# balance.net
KiCad netlist of a schematic drawn in EAGLE
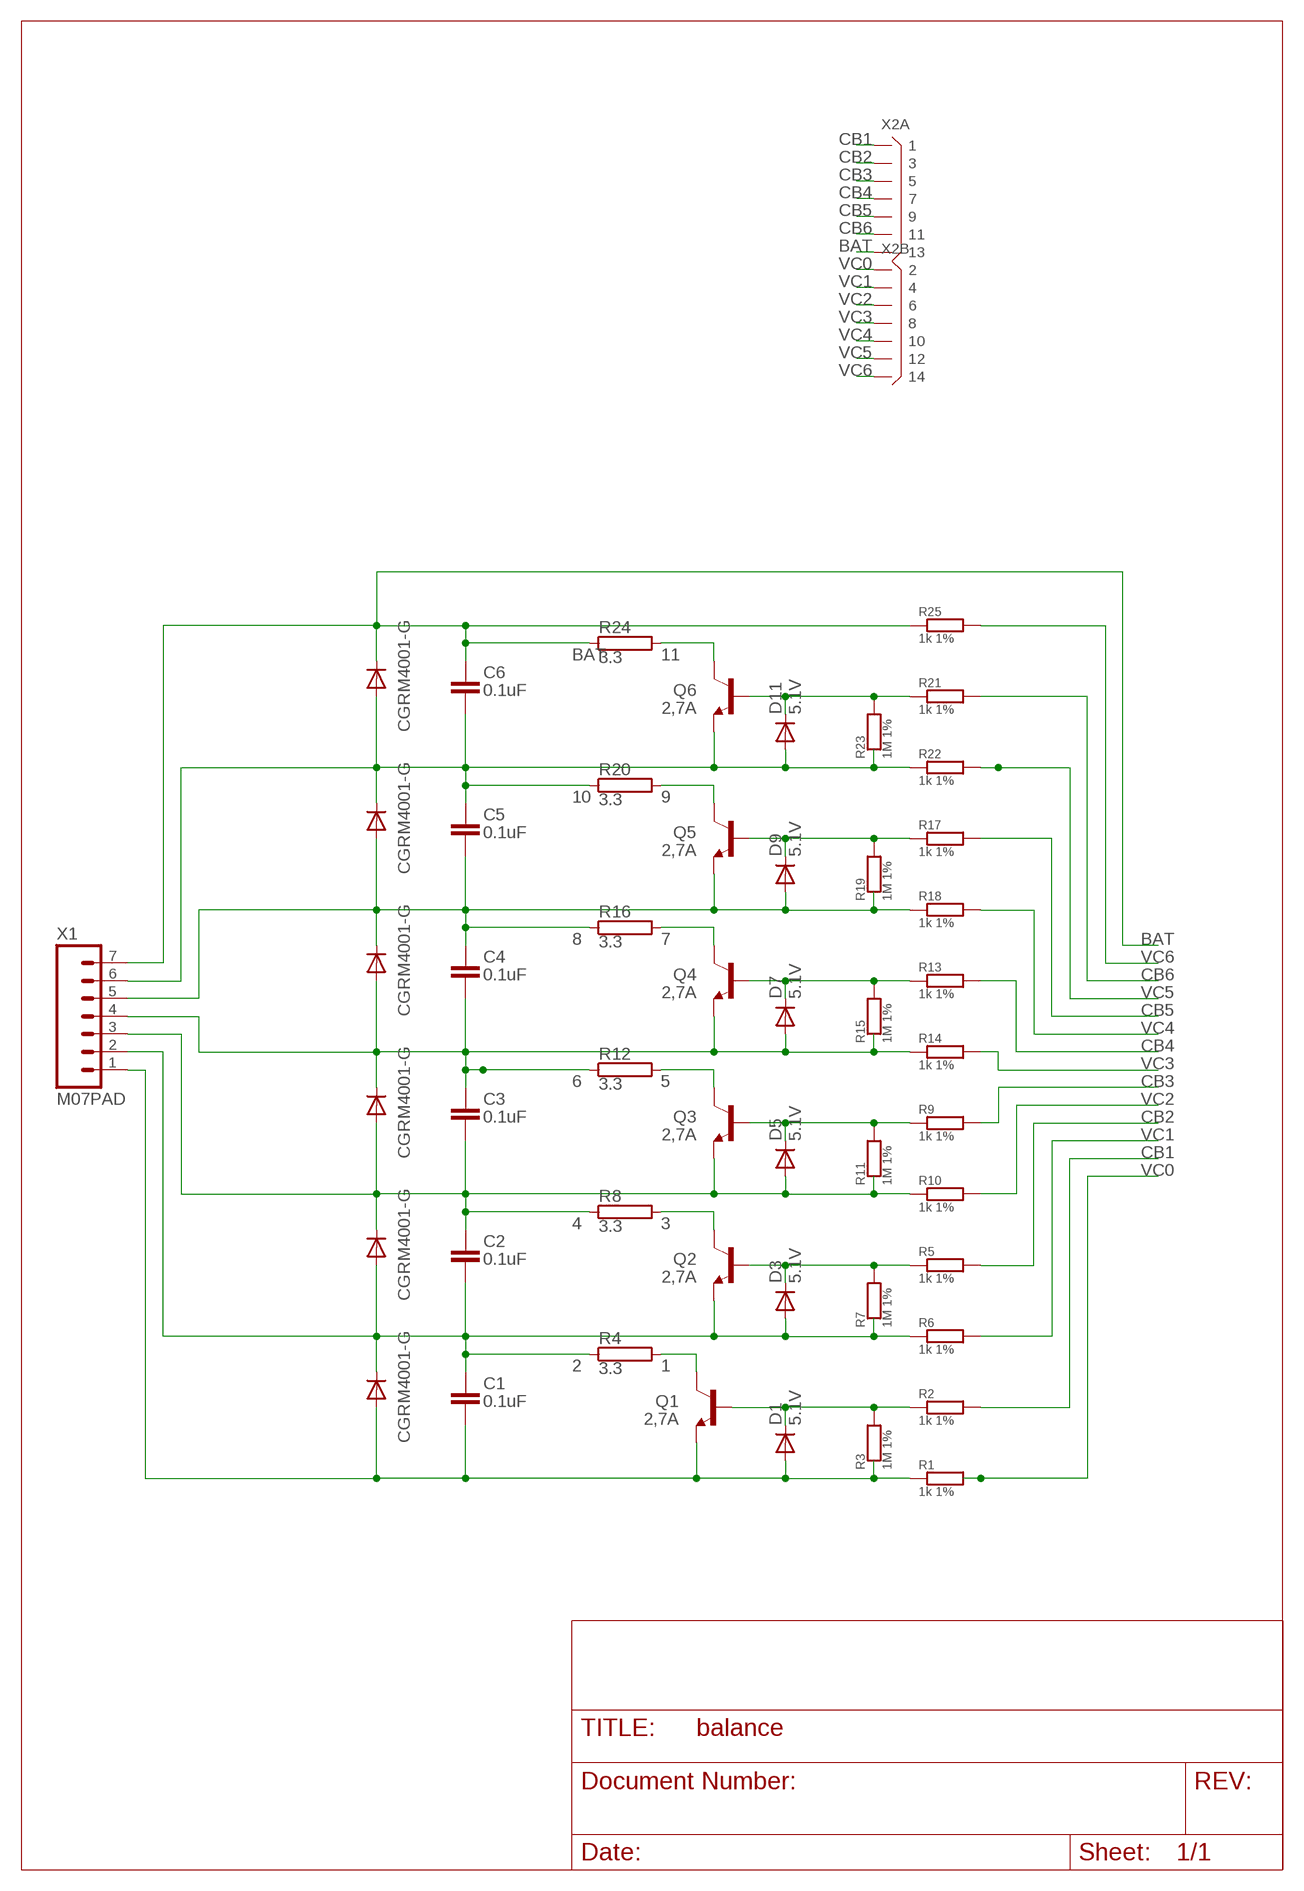
[diagram p0: schematic, sheet 1]

(export (version "E")
  (design (tool "Eeschema 10.0.6"))
  (components
    (comp (ref "C1")
      (value "0.1uF")
      (footprint "eagle-import:C0805")
      (libsource (lib "eagle-import") (part "CSTD"))
    )
    (comp (ref "C2")
      (value "0.1uF")
      (footprint "eagle-import:C0805")
      (libsource (lib "eagle-import") (part "CSTD"))
    )
    (comp (ref "C3")
      (value "0.1uF")
      (footprint "eagle-import:C0805")
      (libsource (lib "eagle-import") (part "CSTD"))
    )
    (comp (ref "C4")
      (value "0.1uF")
      (footprint "eagle-import:C0805")
      (libsource (lib "eagle-import") (part "CSTD"))
    )
    (comp (ref "C5")
      (value "0.1uF")
      (footprint "eagle-import:C0805")
      (libsource (lib "eagle-import") (part "CSTD"))
    )
    (comp (ref "C6")
      (value "0.1uF")
      (footprint "eagle-import:C0805")
      (libsource (lib "eagle-import") (part "CSTD"))
    )
    (comp (ref "D1")
      (value "5.1V")
      (footprint "eagle-import:SOD-323")
      (libsource (lib "eagle-import") (part "DIODESOD"))
    )
    (comp (ref "D2")
      (value "CGRM4001-G")
      (footprint "eagle-import:SOD-123_MINI-SMA")
      (libsource (lib "eagle-import") (part "CGRM400-G1"))
    )
    (comp (ref "D3")
      (value "5.1V")
      (footprint "eagle-import:SOD-323")
      (libsource (lib "eagle-import") (part "DIODESOD"))
    )
    (comp (ref "D4")
      (value "CGRM4001-G")
      (footprint "eagle-import:SOD-123_MINI-SMA")
      (libsource (lib "eagle-import") (part "CGRM400-G1"))
    )
    (comp (ref "D5")
      (value "5.1V")
      (footprint "eagle-import:SOD-323")
      (libsource (lib "eagle-import") (part "DIODESOD"))
    )
    (comp (ref "D6")
      (value "CGRM4001-G")
      (footprint "eagle-import:SOD-123_MINI-SMA")
      (libsource (lib "eagle-import") (part "CGRM400-G1"))
    )
    (comp (ref "D7")
      (value "5.1V")
      (footprint "eagle-import:SOD-323")
      (libsource (lib "eagle-import") (part "DIODESOD"))
    )
    (comp (ref "D8")
      (value "CGRM4001-G")
      (footprint "eagle-import:SOD-123_MINI-SMA")
      (libsource (lib "eagle-import") (part "CGRM400-G1"))
    )
    (comp (ref "D9")
      (value "5.1V")
      (footprint "eagle-import:SOD-323")
      (libsource (lib "eagle-import") (part "DIODESOD"))
    )
    (comp (ref "D10")
      (value "CGRM4001-G")
      (footprint "eagle-import:SOD-123_MINI-SMA")
      (libsource (lib "eagle-import") (part "CGRM400-G1"))
    )
    (comp (ref "D11")
      (value "5.1V")
      (footprint "eagle-import:SOD-323")
      (libsource (lib "eagle-import") (part "DIODESOD"))
    )
    (comp (ref "D12")
      (value "CGRM4001-G")
      (footprint "eagle-import:SOD-123_MINI-SMA")
      (libsource (lib "eagle-import") (part "CGRM400-G1"))
    )
    (comp (ref "Q1")
      (value "2,7A")
      (footprint "eagle-import:SOT23")
      (libsource (lib "eagle-import") (part "TRANSISTOR_NPNSOT23"))
    )
    (comp (ref "Q2")
      (value "2,7A")
      (footprint "eagle-import:SOT23")
      (libsource (lib "eagle-import") (part "TRANSISTOR_NPNSOT23"))
    )
    (comp (ref "Q3")
      (value "2,7A")
      (footprint "eagle-import:SOT23")
      (libsource (lib "eagle-import") (part "TRANSISTOR_NPNSOT23"))
    )
    (comp (ref "Q4")
      (value "2,7A")
      (footprint "eagle-import:SOT23")
      (libsource (lib "eagle-import") (part "TRANSISTOR_NPNSOT23"))
    )
    (comp (ref "Q5")
      (value "2,7A")
      (footprint "eagle-import:SOT23")
      (libsource (lib "eagle-import") (part "TRANSISTOR_NPNSOT23"))
    )
    (comp (ref "Q6")
      (value "2,7A")
      (footprint "eagle-import:SOT23")
      (libsource (lib "eagle-import") (part "TRANSISTOR_NPNSOT23"))
    )
    (comp (ref "R1")
      (value "1k 1%")
      (footprint "eagle-import:R0805")
      (libsource (lib "eagle-import") (part "R"))
    )
    (comp (ref "R2")
      (value "1k 1%")
      (footprint "eagle-import:R0805")
      (libsource (lib "eagle-import") (part "R"))
    )
    (comp (ref "R3")
      (value "1M 1%")
      (footprint "eagle-import:R0805")
      (libsource (lib "eagle-import") (part "R"))
    )
    (comp (ref "R4")
      (value "3.3")
      (footprint "eagle-import:HS15")
      (fields (field (name "MF") "OHMITE") (field (name "MPN") "RHS15KE"))
      (libsource (lib "eagle-import") (part "RHS15"))
    )
    (comp (ref "R5")
      (value "1k 1%")
      (footprint "eagle-import:R0805")
      (libsource (lib "eagle-import") (part "R"))
    )
    (comp (ref "R6")
      (value "1k 1%")
      (footprint "eagle-import:R0805")
      (libsource (lib "eagle-import") (part "R"))
    )
    (comp (ref "R7")
      (value "1M 1%")
      (footprint "eagle-import:R0805")
      (libsource (lib "eagle-import") (part "R"))
    )
    (comp (ref "R8")
      (value "3.3")
      (footprint "eagle-import:HS15")
      (fields (field (name "MF") "OHMITE") (field (name "MPN") "RHS15KE"))
      (libsource (lib "eagle-import") (part "RHS15"))
    )
    (comp (ref "R9")
      (value "1k 1%")
      (footprint "eagle-import:R0805")
      (libsource (lib "eagle-import") (part "R"))
    )
    (comp (ref "R10")
      (value "1k 1%")
      (footprint "eagle-import:R0805")
      (libsource (lib "eagle-import") (part "R"))
    )
    (comp (ref "R11")
      (value "1M 1%")
      (footprint "eagle-import:R0805")
      (libsource (lib "eagle-import") (part "R"))
    )
    (comp (ref "R12")
      (value "3.3")
      (footprint "eagle-import:HS15")
      (fields (field (name "MF") "OHMITE") (field (name "MPN") "RHS15KE"))
      (libsource (lib "eagle-import") (part "RHS15"))
    )
    (comp (ref "R13")
      (value "1k 1%")
      (footprint "eagle-import:R0805")
      (libsource (lib "eagle-import") (part "R"))
    )
    (comp (ref "R14")
      (value "1k 1%")
      (footprint "eagle-import:R0805")
      (libsource (lib "eagle-import") (part "R"))
    )
    (comp (ref "R15")
      (value "1M 1%")
      (footprint "eagle-import:R0805")
      (libsource (lib "eagle-import") (part "R"))
    )
    (comp (ref "R16")
      (value "3.3")
      (footprint "eagle-import:HS15")
      (fields (field (name "MF") "OHMITE") (field (name "MPN") "RHS15KE"))
      (libsource (lib "eagle-import") (part "RHS15"))
    )
    (comp (ref "R17")
      (value "1k 1%")
      (footprint "eagle-import:R0805")
      (libsource (lib "eagle-import") (part "R"))
    )
    (comp (ref "R18")
      (value "1k 1%")
      (footprint "eagle-import:R0805")
      (libsource (lib "eagle-import") (part "R"))
    )
    (comp (ref "R19")
      (value "1M 1%")
      (footprint "eagle-import:R0805")
      (libsource (lib "eagle-import") (part "R"))
    )
    (comp (ref "R20")
      (value "3.3")
      (footprint "eagle-import:HS15")
      (fields (field (name "MF") "OHMITE") (field (name "MPN") "RHS15KE"))
      (libsource (lib "eagle-import") (part "RHS15"))
    )
    (comp (ref "R21")
      (value "1k 1%")
      (footprint "eagle-import:R0805")
      (libsource (lib "eagle-import") (part "R"))
    )
    (comp (ref "R22")
      (value "1k 1%")
      (footprint "eagle-import:R0805")
      (libsource (lib "eagle-import") (part "R"))
    )
    (comp (ref "R23")
      (value "1M 1%")
      (footprint "eagle-import:R0805")
      (libsource (lib "eagle-import") (part "R"))
    )
    (comp (ref "R24")
      (value "3.3")
      (footprint "eagle-import:HS15")
      (fields (field (name "MF") "OHMITE") (field (name "MPN") "RHS15KE"))
      (libsource (lib "eagle-import") (part "RHS15"))
    )
    (comp (ref "R25")
      (value "1k 1%")
      (footprint "eagle-import:R0805")
      (libsource (lib "eagle-import") (part "R"))
    )
    (comp (ref "X1")
      (value "M07PAD")
      (footprint "eagle-import:1X07")
      (libsource (lib "eagle-import") (part "M07PAD"))
    )
    (comp (ref "X2")
      (value "X07X2IR")
      (footprint "eagle-import:X14R-IDC")
      (libsource (lib "eagle-import") (part "X07X2IR"))
    )
  )
  (nets
    (net (code "1") (name "/1") (class "Default")
      (node (ref "Q1") (pin "3") (pinfunction "C_3") (pintype "passive"))
      (node (ref "R4") (pin "2") (pinfunction "2_2") (pintype "passive"))
    )
    (net (code "2") (name "/2") (class "Default")
      (node (ref "C1") (pin "2") (pinfunction "2_2") (pintype "passive"))
      (node (ref "C2") (pin "1") (pinfunction "1_1") (pintype "passive"))
      (node (ref "D2") (pin "C") (pinfunction "C_C") (pintype "passive"))
      (node (ref "D3") (pin "2") (pinfunction "A_2") (pintype "passive"))
      (node (ref "D4") (pin "A") (pinfunction "A_A") (pintype "passive"))
      (node (ref "Q2") (pin "2") (pinfunction "E_2") (pintype "passive"))
      (node (ref "R4") (pin "1") (pinfunction "1_1") (pintype "passive"))
      (node (ref "R6") (pin "1") (pinfunction "1_1") (pintype "passive"))
      (node (ref "R7") (pin "1") (pinfunction "1_1") (pintype "passive"))
      (node (ref "X1") (pin "2") (pinfunction "2_2") (pintype "passive"))
    )
    (net (code "3") (name "/3") (class "Default")
      (node (ref "Q2") (pin "3") (pinfunction "C_3") (pintype "passive"))
      (node (ref "R8") (pin "2") (pinfunction "2_2") (pintype "passive"))
    )
    (net (code "4") (name "/4") (class "Default")
      (node (ref "C2") (pin "2") (pinfunction "2_2") (pintype "passive"))
      (node (ref "C3") (pin "1") (pinfunction "1_1") (pintype "passive"))
      (node (ref "D4") (pin "C") (pinfunction "C_C") (pintype "passive"))
      (node (ref "D5") (pin "2") (pinfunction "A_2") (pintype "passive"))
      (node (ref "D6") (pin "A") (pinfunction "A_A") (pintype "passive"))
      (node (ref "Q3") (pin "2") (pinfunction "E_2") (pintype "passive"))
      (node (ref "R10") (pin "1") (pinfunction "1_1") (pintype "passive"))
      (node (ref "R11") (pin "1") (pinfunction "1_1") (pintype "passive"))
      (node (ref "R8") (pin "1") (pinfunction "1_1") (pintype "passive"))
      (node (ref "X1") (pin "3") (pinfunction "3_3") (pintype "passive"))
    )
    (net (code "5") (name "/5") (class "Default")
      (node (ref "Q3") (pin "3") (pinfunction "C_3") (pintype "passive"))
      (node (ref "R12") (pin "2") (pinfunction "2_2") (pintype "passive"))
    )
    (net (code "6") (name "/6") (class "Default")
      (node (ref "C3") (pin "2") (pinfunction "2_2") (pintype "passive"))
      (node (ref "C4") (pin "1") (pinfunction "1_1") (pintype "passive"))
      (node (ref "D6") (pin "C") (pinfunction "C_C") (pintype "passive"))
      (node (ref "D7") (pin "2") (pinfunction "A_2") (pintype "passive"))
      (node (ref "D8") (pin "A") (pinfunction "A_A") (pintype "passive"))
      (node (ref "Q4") (pin "2") (pinfunction "E_2") (pintype "passive"))
      (node (ref "R12") (pin "1") (pinfunction "1_1") (pintype "passive"))
      (node (ref "R14") (pin "1") (pinfunction "1_1") (pintype "passive"))
      (node (ref "R15") (pin "1") (pinfunction "1_1") (pintype "passive"))
      (node (ref "X1") (pin "4") (pinfunction "4_4") (pintype "passive"))
    )
    (net (code "7") (name "/7") (class "Default")
      (node (ref "Q4") (pin "3") (pinfunction "C_3") (pintype "passive"))
      (node (ref "R16") (pin "2") (pinfunction "2_2") (pintype "passive"))
    )
    (net (code "8") (name "/8") (class "Default")
      (node (ref "C4") (pin "2") (pinfunction "2_2") (pintype "passive"))
      (node (ref "C5") (pin "1") (pinfunction "1_1") (pintype "passive"))
      (node (ref "D10") (pin "A") (pinfunction "A_A") (pintype "passive"))
      (node (ref "D8") (pin "C") (pinfunction "C_C") (pintype "passive"))
      (node (ref "D9") (pin "2") (pinfunction "A_2") (pintype "passive"))
      (node (ref "Q5") (pin "2") (pinfunction "E_2") (pintype "passive"))
      (node (ref "R16") (pin "1") (pinfunction "1_1") (pintype "passive"))
      (node (ref "R18") (pin "1") (pinfunction "1_1") (pintype "passive"))
      (node (ref "R19") (pin "1") (pinfunction "1_1") (pintype "passive"))
      (node (ref "X1") (pin "5") (pinfunction "5_5") (pintype "passive"))
    )
    (net (code "9") (name "/9") (class "Default")
      (node (ref "Q5") (pin "3") (pinfunction "C_3") (pintype "passive"))
      (node (ref "R20") (pin "2") (pinfunction "2_2") (pintype "passive"))
    )
    (net (code "10") (name "/10") (class "Default")
      (node (ref "C5") (pin "2") (pinfunction "2_2") (pintype "passive"))
      (node (ref "C6") (pin "1") (pinfunction "1_1") (pintype "passive"))
      (node (ref "D10") (pin "C") (pinfunction "C_C") (pintype "passive"))
      (node (ref "D11") (pin "2") (pinfunction "A_2") (pintype "passive"))
      (node (ref "D12") (pin "A") (pinfunction "A_A") (pintype "passive"))
      (node (ref "Q6") (pin "2") (pinfunction "E_2") (pintype "passive"))
      (node (ref "R20") (pin "1") (pinfunction "1_1") (pintype "passive"))
      (node (ref "R22") (pin "1") (pinfunction "1_1") (pintype "passive"))
      (node (ref "R23") (pin "1") (pinfunction "1_1") (pintype "passive"))
      (node (ref "X1") (pin "6") (pinfunction "6_6") (pintype "passive"))
    )
    (net (code "11") (name "/11") (class "Default")
      (node (ref "Q6") (pin "3") (pinfunction "C_3") (pintype "passive"))
      (node (ref "R24") (pin "2") (pinfunction "2_2") (pintype "passive"))
    )
    (net (code "12") (name "/BAT") (class "Default")
      (node (ref "C6") (pin "2") (pinfunction "2_2") (pintype "passive"))
      (node (ref "D12") (pin "C") (pinfunction "C_C") (pintype "passive"))
      (node (ref "R24") (pin "1") (pinfunction "1_1") (pintype "passive"))
      (node (ref "R25") (pin "1") (pinfunction "1_1") (pintype "passive"))
      (node (ref "X1") (pin "7") (pinfunction "7_7") (pintype "passive"))
      (node (ref "X2") (pin "13") (pinfunction "13_13") (pintype "bidirectional"))
    )
    (net (code "13") (name "/CB1") (class "Default")
      (node (ref "R2") (pin "2") (pinfunction "2_2") (pintype "passive"))
      (node (ref "X2") (pin "1") (pinfunction "1_1") (pintype "bidirectional"))
    )
    (net (code "14") (name "/CB2") (class "Default")
      (node (ref "R5") (pin "2") (pinfunction "2_2") (pintype "passive"))
      (node (ref "X2") (pin "3") (pinfunction "3_3") (pintype "bidirectional"))
    )
    (net (code "15") (name "/CB3") (class "Default")
      (node (ref "R9") (pin "2") (pinfunction "2_2") (pintype "passive"))
      (node (ref "X2") (pin "5") (pinfunction "5_5") (pintype "bidirectional"))
    )
    (net (code "16") (name "/CB4") (class "Default")
      (node (ref "R13") (pin "2") (pinfunction "2_2") (pintype "passive"))
      (node (ref "X2") (pin "7") (pinfunction "7_7") (pintype "bidirectional"))
    )
    (net (code "17") (name "/CB5") (class "Default")
      (node (ref "R17") (pin "2") (pinfunction "2_2") (pintype "passive"))
      (node (ref "X2") (pin "9") (pinfunction "9_9") (pintype "bidirectional"))
    )
    (net (code "18") (name "/CB6") (class "Default")
      (node (ref "R21") (pin "2") (pinfunction "2_2") (pintype "passive"))
      (node (ref "X2") (pin "11") (pinfunction "11_11") (pintype "bidirectional"))
    )
    (net (code "19") (name "/VC0") (class "Default")
      (node (ref "R1") (pin "2") (pinfunction "2_2") (pintype "passive"))
      (node (ref "X2") (pin "2") (pinfunction "2_2") (pintype "bidirectional"))
    )
    (net (code "20") (name "/VC1") (class "Default")
      (node (ref "R6") (pin "2") (pinfunction "2_2") (pintype "passive"))
      (node (ref "X2") (pin "4") (pinfunction "4_4") (pintype "bidirectional"))
    )
    (net (code "21") (name "/VC2") (class "Default")
      (node (ref "R10") (pin "2") (pinfunction "2_2") (pintype "passive"))
      (node (ref "X2") (pin "6") (pinfunction "6_6") (pintype "bidirectional"))
    )
    (net (code "22") (name "/VC3") (class "Default")
      (node (ref "R14") (pin "2") (pinfunction "2_2") (pintype "passive"))
      (node (ref "X2") (pin "8") (pinfunction "8_8") (pintype "bidirectional"))
    )
    (net (code "23") (name "/VC4") (class "Default")
      (node (ref "R18") (pin "2") (pinfunction "2_2") (pintype "passive"))
      (node (ref "X2") (pin "10") (pinfunction "10_10") (pintype "bidirectional"))
    )
    (net (code "24") (name "/VC5") (class "Default")
      (node (ref "R22") (pin "2") (pinfunction "2_2") (pintype "passive"))
      (node (ref "X2") (pin "12") (pinfunction "12_12") (pintype "bidirectional"))
    )
    (net (code "25") (name "/VC6") (class "Default")
      (node (ref "R25") (pin "2") (pinfunction "2_2") (pintype "passive"))
      (node (ref "X2") (pin "14") (pinfunction "14_14") (pintype "bidirectional"))
    )
    (net (code "26") (name "Net-(D1-A)") (class "Default")
      (node (ref "C1") (pin "1") (pinfunction "1_1") (pintype "passive"))
      (node (ref "D1") (pin "2") (pinfunction "A_2") (pintype "passive"))
      (node (ref "D2") (pin "A") (pinfunction "A_A") (pintype "passive"))
      (node (ref "Q1") (pin "2") (pinfunction "E_2") (pintype "passive"))
      (node (ref "R1") (pin "1") (pinfunction "1_1") (pintype "passive"))
      (node (ref "R3") (pin "1") (pinfunction "1_1") (pintype "passive"))
      (node (ref "X1") (pin "1") (pinfunction "1_1") (pintype "passive"))
    )
    (net (code "27") (name "Net-(D1-C)") (class "Default")
      (node (ref "D1") (pin "1") (pinfunction "C_1") (pintype "passive"))
      (node (ref "Q1") (pin "1") (pinfunction "B_1") (pintype "passive"))
      (node (ref "R2") (pin "1") (pinfunction "1_1") (pintype "passive"))
      (node (ref "R3") (pin "2") (pinfunction "2_2") (pintype "passive"))
    )
    (net (code "28") (name "Net-(D3-C)") (class "Default")
      (node (ref "D3") (pin "1") (pinfunction "C_1") (pintype "passive"))
      (node (ref "Q2") (pin "1") (pinfunction "B_1") (pintype "passive"))
      (node (ref "R5") (pin "1") (pinfunction "1_1") (pintype "passive"))
      (node (ref "R7") (pin "2") (pinfunction "2_2") (pintype "passive"))
    )
    (net (code "29") (name "Net-(D5-C)") (class "Default")
      (node (ref "D5") (pin "1") (pinfunction "C_1") (pintype "passive"))
      (node (ref "Q3") (pin "1") (pinfunction "B_1") (pintype "passive"))
      (node (ref "R11") (pin "2") (pinfunction "2_2") (pintype "passive"))
      (node (ref "R9") (pin "1") (pinfunction "1_1") (pintype "passive"))
    )
    (net (code "30") (name "Net-(D7-C)") (class "Default")
      (node (ref "D7") (pin "1") (pinfunction "C_1") (pintype "passive"))
      (node (ref "Q4") (pin "1") (pinfunction "B_1") (pintype "passive"))
      (node (ref "R13") (pin "1") (pinfunction "1_1") (pintype "passive"))
      (node (ref "R15") (pin "2") (pinfunction "2_2") (pintype "passive"))
    )
    (net (code "31") (name "Net-(D9-C)") (class "Default")
      (node (ref "D9") (pin "1") (pinfunction "C_1") (pintype "passive"))
      (node (ref "Q5") (pin "1") (pinfunction "B_1") (pintype "passive"))
      (node (ref "R17") (pin "1") (pinfunction "1_1") (pintype "passive"))
      (node (ref "R19") (pin "2") (pinfunction "2_2") (pintype "passive"))
    )
    (net (code "32") (name "Net-(D11-C)") (class "Default")
      (node (ref "D11") (pin "1") (pinfunction "C_1") (pintype "passive"))
      (node (ref "Q6") (pin "1") (pinfunction "B_1") (pintype "passive"))
      (node (ref "R21") (pin "1") (pinfunction "1_1") (pintype "passive"))
      (node (ref "R23") (pin "2") (pinfunction "2_2") (pintype "passive"))
    )
  )
)
